# sensor_only.net
KiCad netlist of a schematic drawn in EAGLE
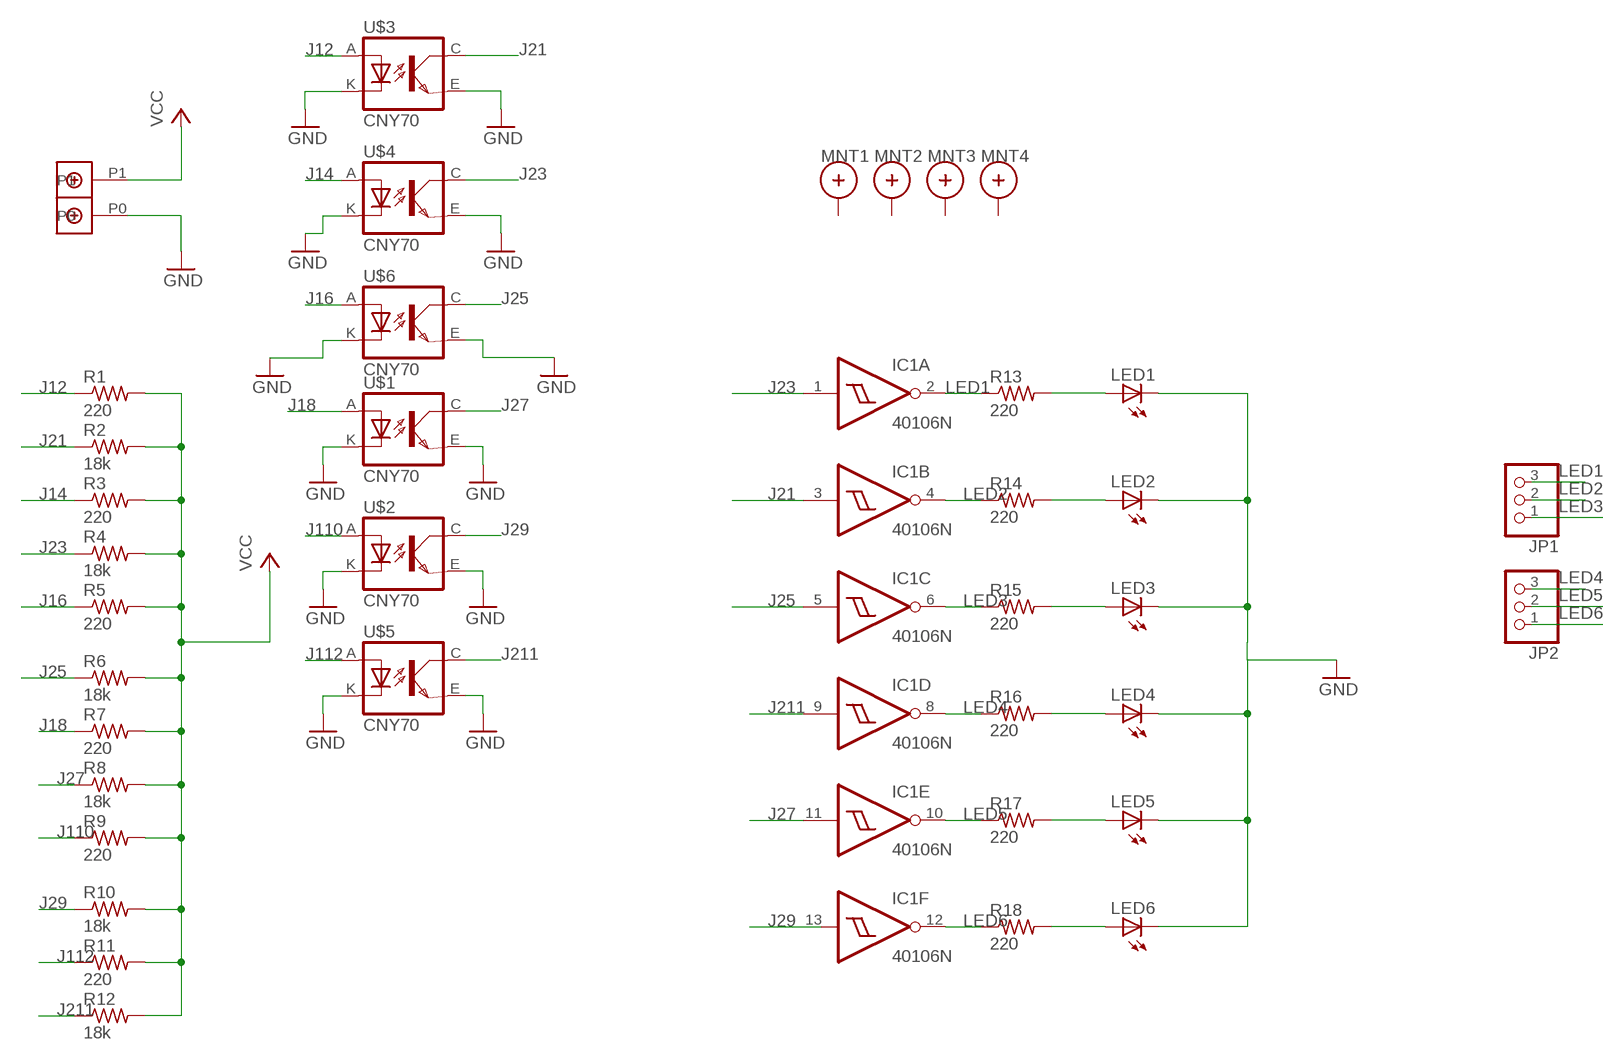
[diagram p0: schematic, sheet 1]

(export (version "E")
  (design (tool "Eeschema 10.0.6"))
  (components
    (comp (ref "IC1")
      (value "40106N")
      (footprint "eagle-import:DIL14")
      (libsource (lib "eagle-import") (part "40106N"))
    )
    (comp (ref "JP1")
      (value "PINHD-1X3")
      (footprint "eagle-import:1X03")
      (libsource (lib "eagle-import") (part "PINHD-1X3"))
    )
    (comp (ref "JP2")
      (value "PINHD-1X3")
      (footprint "eagle-import:1X03")
      (libsource (lib "eagle-import") (part "PINHD-1X3"))
    )
    (comp (ref "LED1")
      (value "LEDCHIPLED_1206")
      (footprint "eagle-import:CHIPLED_1206")
      (libsource (lib "eagle-import") (part "LEDCHIPLED_1206"))
    )
    (comp (ref "LED2")
      (value "LEDCHIPLED_1206")
      (footprint "eagle-import:CHIPLED_1206")
      (libsource (lib "eagle-import") (part "LEDCHIPLED_1206"))
    )
    (comp (ref "LED3")
      (value "LEDCHIPLED_1206")
      (footprint "eagle-import:CHIPLED_1206")
      (libsource (lib "eagle-import") (part "LEDCHIPLED_1206"))
    )
    (comp (ref "LED4")
      (value "LEDCHIPLED_1206")
      (footprint "eagle-import:CHIPLED_1206")
      (libsource (lib "eagle-import") (part "LEDCHIPLED_1206"))
    )
    (comp (ref "LED5")
      (value "LEDCHIPLED_1206")
      (footprint "eagle-import:CHIPLED_1206")
      (libsource (lib "eagle-import") (part "LEDCHIPLED_1206"))
    )
    (comp (ref "LED6")
      (value "LEDCHIPLED_1206")
      (footprint "eagle-import:CHIPLED_1206")
      (libsource (lib "eagle-import") (part "LEDCHIPLED_1206"))
    )
    (comp (ref "MNT1")
      (value "HOLE_MNT_0.135")
      (footprint "eagle-import:HOLE_MNT_#5-40")
      (libsource (lib "eagle-import") (part "HOLE_MNT_0.135"))
    )
    (comp (ref "MNT2")
      (value "HOLE_MNT_0.135")
      (footprint "eagle-import:HOLE_MNT_#5-40")
      (libsource (lib "eagle-import") (part "HOLE_MNT_0.135"))
    )
    (comp (ref "MNT3")
      (value "HOLE_MNT_0.135")
      (footprint "eagle-import:HOLE_MNT_#5-40")
      (libsource (lib "eagle-import") (part "HOLE_MNT_0.135"))
    )
    (comp (ref "MNT4")
      (value "HOLE_MNT_0.135")
      (footprint "eagle-import:HOLE_MNT_#5-40")
      (libsource (lib "eagle-import") (part "HOLE_MNT_0.135"))
    )
    (comp (ref "R1")
      (value "220")
      (footprint "eagle-import:M1206")
      (libsource (lib "eagle-import") (part "R-US_M1206"))
    )
    (comp (ref "R2")
      (value "18k")
      (footprint "eagle-import:M1206")
      (libsource (lib "eagle-import") (part "R-US_M1206"))
    )
    (comp (ref "R3")
      (value "220")
      (footprint "eagle-import:M1206")
      (libsource (lib "eagle-import") (part "R-US_M1206"))
    )
    (comp (ref "R4")
      (value "18k")
      (footprint "eagle-import:M1206")
      (libsource (lib "eagle-import") (part "R-US_M1206"))
    )
    (comp (ref "R5")
      (value "220")
      (footprint "eagle-import:M1206")
      (libsource (lib "eagle-import") (part "R-US_M1206"))
    )
    (comp (ref "R6")
      (value "18k")
      (footprint "eagle-import:M1206")
      (libsource (lib "eagle-import") (part "R-US_M1206"))
    )
    (comp (ref "R7")
      (value "220")
      (footprint "eagle-import:M1206")
      (libsource (lib "eagle-import") (part "R-US_M1206"))
    )
    (comp (ref "R8")
      (value "18k")
      (footprint "eagle-import:M1206")
      (libsource (lib "eagle-import") (part "R-US_M1206"))
    )
    (comp (ref "R9")
      (value "220")
      (footprint "eagle-import:M1206")
      (libsource (lib "eagle-import") (part "R-US_M1206"))
    )
    (comp (ref "R10")
      (value "18k")
      (footprint "eagle-import:M1206")
      (libsource (lib "eagle-import") (part "R-US_M1206"))
    )
    (comp (ref "R11")
      (value "220")
      (footprint "eagle-import:M1206")
      (libsource (lib "eagle-import") (part "R-US_M1206"))
    )
    (comp (ref "R12")
      (value "18k")
      (footprint "eagle-import:M1206")
      (libsource (lib "eagle-import") (part "R-US_M1206"))
    )
    (comp (ref "R13")
      (value "220")
      (footprint "eagle-import:M1206")
      (libsource (lib "eagle-import") (part "R-US_M1206"))
    )
    (comp (ref "R14")
      (value "220")
      (footprint "eagle-import:M1206")
      (libsource (lib "eagle-import") (part "R-US_M1206"))
    )
    (comp (ref "R15")
      (value "220")
      (footprint "eagle-import:M1206")
      (libsource (lib "eagle-import") (part "R-US_M1206"))
    )
    (comp (ref "R16")
      (value "220")
      (footprint "eagle-import:M1206")
      (libsource (lib "eagle-import") (part "R-US_M1206"))
    )
    (comp (ref "R17")
      (value "220")
      (footprint "eagle-import:M1206")
      (libsource (lib "eagle-import") (part "R-US_M1206"))
    )
    (comp (ref "R18")
      (value "220")
      (footprint "eagle-import:M1206")
      (libsource (lib "eagle-import") (part "R-US_M1206"))
    )
    (comp (ref "U$1")
      (value "CNY70")
      (footprint "eagle-import:4")
      (libsource (lib "eagle-import") (part "CNY70"))
    )
    (comp (ref "U$2")
      (value "CNY70")
      (footprint "eagle-import:4")
      (libsource (lib "eagle-import") (part "CNY70"))
    )
    (comp (ref "U$3")
      (value "CNY70")
      (footprint "eagle-import:4")
      (libsource (lib "eagle-import") (part "CNY70"))
    )
    (comp (ref "U$4")
      (value "CNY70")
      (footprint "eagle-import:4")
      (libsource (lib "eagle-import") (part "CNY70"))
    )
    (comp (ref "U$5")
      (value "CNY70")
      (footprint "eagle-import:4")
      (libsource (lib "eagle-import") (part "CNY70"))
    )
    (comp (ref "U$6")
      (value "CNY70")
      (footprint "eagle-import:4")
      (libsource (lib "eagle-import") (part "CNY70"))
    )
    (comp (ref "U$7")
      (value "DBCONN-1X2")
      (footprint "eagle-import:DBCONN-1X2")
      (libsource (lib "eagle-import") (part "DBCONN-1X2"))
    )
  )
  (nets
    (net (code "1") (name "/J12") (class "Default")
      (node (ref "R1") (pin "1") (pinfunction "1_1") (pintype "passive"))
      (node (ref "U$3") (pin "A") (pinfunction "A_A") (pintype "passive"))
    )
    (net (code "2") (name "/J14") (class "Default")
      (node (ref "R3") (pin "1") (pinfunction "1_1") (pintype "passive"))
      (node (ref "U$4") (pin "A") (pinfunction "A_A") (pintype "passive"))
    )
    (net (code "3") (name "/J16") (class "Default")
      (node (ref "R5") (pin "1") (pinfunction "1_1") (pintype "passive"))
      (node (ref "U$6") (pin "A") (pinfunction "A_A") (pintype "passive"))
    )
    (net (code "4") (name "/J18") (class "Default")
      (node (ref "R7") (pin "1") (pinfunction "1_1") (pintype "passive"))
      (node (ref "U$1") (pin "A") (pinfunction "A_A") (pintype "passive"))
    )
    (net (code "5") (name "/J21") (class "Default")
      (node (ref "IC1") (pin "3") (pinfunction "I_3") (pintype "input"))
      (node (ref "R2") (pin "1") (pinfunction "1_1") (pintype "passive"))
      (node (ref "U$3") (pin "C") (pinfunction "COL_C") (pintype "passive"))
    )
    (net (code "6") (name "/J23") (class "Default")
      (node (ref "IC1") (pin "1") (pinfunction "I_1") (pintype "input"))
      (node (ref "R4") (pin "1") (pinfunction "1_1") (pintype "passive"))
      (node (ref "U$4") (pin "C") (pinfunction "COL_C") (pintype "passive"))
    )
    (net (code "7") (name "/J25") (class "Default")
      (node (ref "IC1") (pin "5") (pinfunction "I_5") (pintype "input"))
      (node (ref "R6") (pin "1") (pinfunction "1_1") (pintype "passive"))
      (node (ref "U$6") (pin "C") (pinfunction "COL_C") (pintype "passive"))
    )
    (net (code "8") (name "/J27") (class "Default")
      (node (ref "IC1") (pin "11") (pinfunction "I_11") (pintype "input"))
      (node (ref "R8") (pin "1") (pinfunction "1_1") (pintype "passive"))
      (node (ref "U$1") (pin "C") (pinfunction "COL_C") (pintype "passive"))
    )
    (net (code "9") (name "/J29") (class "Default")
      (node (ref "R10") (pin "1") (pinfunction "1_1") (pintype "passive"))
      (node (ref "U$2") (pin "C") (pinfunction "COL_C") (pintype "passive"))
    )
    (net (code "10") (name "/J110") (class "Default")
      (node (ref "R9") (pin "1") (pinfunction "1_1") (pintype "passive"))
      (node (ref "U$2") (pin "A") (pinfunction "A_A") (pintype "passive"))
    )
    (net (code "11") (name "/J112") (class "Default")
      (node (ref "R11") (pin "1") (pinfunction "1_1") (pintype "passive"))
      (node (ref "U$5") (pin "A") (pinfunction "A_A") (pintype "passive"))
    )
    (net (code "12") (name "/J211") (class "Default")
      (node (ref "IC1") (pin "9") (pinfunction "I_9") (pintype "input"))
      (node (ref "R12") (pin "1") (pinfunction "1_1") (pintype "passive"))
      (node (ref "U$5") (pin "C") (pinfunction "COL_C") (pintype "passive"))
    )
    (net (code "13") (name "/LED1") (class "Default")
      (node (ref "IC1") (pin "2") (pinfunction "O_2") (pintype "output"))
      (node (ref "JP1") (pin "3") (pinfunction "3_3") (pintype "passive"))
      (node (ref "R13") (pin "1") (pinfunction "1_1") (pintype "passive"))
    )
    (net (code "14") (name "/LED2") (class "Default")
      (node (ref "IC1") (pin "4") (pinfunction "O_4") (pintype "output"))
      (node (ref "JP1") (pin "2") (pinfunction "2_2") (pintype "passive"))
      (node (ref "R14") (pin "1") (pinfunction "1_1") (pintype "passive"))
    )
    (net (code "15") (name "/LED3") (class "Default")
      (node (ref "IC1") (pin "6") (pinfunction "O_6") (pintype "output"))
      (node (ref "JP1") (pin "1") (pinfunction "1_1") (pintype "passive"))
      (node (ref "R15") (pin "1") (pinfunction "1_1") (pintype "passive"))
    )
    (net (code "16") (name "/LED4") (class "Default")
      (node (ref "IC1") (pin "8") (pinfunction "O_8") (pintype "output"))
      (node (ref "JP2") (pin "3") (pinfunction "3_3") (pintype "passive"))
      (node (ref "R16") (pin "1") (pinfunction "1_1") (pintype "passive"))
    )
    (net (code "17") (name "/LED5") (class "Default")
      (node (ref "IC1") (pin "10") (pinfunction "O_10") (pintype "output"))
      (node (ref "JP2") (pin "2") (pinfunction "2_2") (pintype "passive"))
      (node (ref "R17") (pin "1") (pinfunction "1_1") (pintype "passive"))
    )
    (net (code "18") (name "/LED6") (class "Default")
      (node (ref "IC1") (pin "12") (pinfunction "O_12") (pintype "output"))
      (node (ref "JP2") (pin "1") (pinfunction "1_1") (pintype "passive"))
      (node (ref "R18") (pin "1") (pinfunction "1_1") (pintype "passive"))
    )
    (net (code "19") (name "GND") (class "Default")
      (node (ref "LED1") (pin "C") (pinfunction "C_C") (pintype "passive"))
      (node (ref "LED2") (pin "C") (pinfunction "C_C") (pintype "passive"))
      (node (ref "LED3") (pin "C") (pinfunction "C_C") (pintype "passive"))
      (node (ref "LED4") (pin "C") (pinfunction "C_C") (pintype "passive"))
      (node (ref "LED5") (pin "C") (pinfunction "C_C") (pintype "passive"))
      (node (ref "LED6") (pin "C") (pinfunction "C_C") (pintype "passive"))
      (node (ref "U$1") (pin "E") (pinfunction "EMI_E") (pintype "passive"))
      (node (ref "U$1") (pin "K") (pinfunction "C_K") (pintype "passive"))
      (node (ref "U$2") (pin "E") (pinfunction "EMI_E") (pintype "passive"))
      (node (ref "U$2") (pin "K") (pinfunction "C_K") (pintype "passive"))
      (node (ref "U$3") (pin "E") (pinfunction "EMI_E") (pintype "passive"))
      (node (ref "U$3") (pin "K") (pinfunction "C_K") (pintype "passive"))
      (node (ref "U$4") (pin "E") (pinfunction "EMI_E") (pintype "passive"))
      (node (ref "U$4") (pin "K") (pinfunction "C_K") (pintype "passive"))
      (node (ref "U$5") (pin "E") (pinfunction "EMI_E") (pintype "passive"))
      (node (ref "U$5") (pin "K") (pinfunction "C_K") (pintype "passive"))
      (node (ref "U$6") (pin "E") (pinfunction "EMI_E") (pintype "passive"))
      (node (ref "U$6") (pin "K") (pinfunction "C_K") (pintype "passive"))
      (node (ref "U$7") (pin "P0") (pinfunction "P0_P0") (pintype "bidirectional"))
    )
    (net (code "20") (name "Net-(LED1-PadA)") (class "Default")
      (node (ref "LED1") (pin "A") (pinfunction "A_A") (pintype "passive"))
      (node (ref "R13") (pin "2") (pinfunction "2_2") (pintype "passive"))
    )
    (net (code "21") (name "Net-(LED2-PadA)") (class "Default")
      (node (ref "LED2") (pin "A") (pinfunction "A_A") (pintype "passive"))
      (node (ref "R14") (pin "2") (pinfunction "2_2") (pintype "passive"))
    )
    (net (code "22") (name "Net-(LED3-PadA)") (class "Default")
      (node (ref "LED3") (pin "A") (pinfunction "A_A") (pintype "passive"))
      (node (ref "R15") (pin "2") (pinfunction "2_2") (pintype "passive"))
    )
    (net (code "23") (name "Net-(LED4-PadA)") (class "Default")
      (node (ref "LED4") (pin "A") (pinfunction "A_A") (pintype "passive"))
      (node (ref "R16") (pin "2") (pinfunction "2_2") (pintype "passive"))
    )
    (net (code "24") (name "Net-(LED5-PadA)") (class "Default")
      (node (ref "LED5") (pin "A") (pinfunction "A_A") (pintype "passive"))
      (node (ref "R17") (pin "2") (pinfunction "2_2") (pintype "passive"))
    )
    (net (code "25") (name "Net-(LED6-PadA)") (class "Default")
      (node (ref "LED6") (pin "A") (pinfunction "A_A") (pintype "passive"))
      (node (ref "R18") (pin "2") (pinfunction "2_2") (pintype "passive"))
    )
    (net (code "26") (name "VCC") (class "Default")
      (node (ref "R1") (pin "2") (pinfunction "2_2") (pintype "passive"))
      (node (ref "R10") (pin "2") (pinfunction "2_2") (pintype "passive"))
      (node (ref "R11") (pin "2") (pinfunction "2_2") (pintype "passive"))
      (node (ref "R12") (pin "2") (pinfunction "2_2") (pintype "passive"))
      (node (ref "R2") (pin "2") (pinfunction "2_2") (pintype "passive"))
      (node (ref "R3") (pin "2") (pinfunction "2_2") (pintype "passive"))
      (node (ref "R4") (pin "2") (pinfunction "2_2") (pintype "passive"))
      (node (ref "R5") (pin "2") (pinfunction "2_2") (pintype "passive"))
      (node (ref "R6") (pin "2") (pinfunction "2_2") (pintype "passive"))
      (node (ref "R7") (pin "2") (pinfunction "2_2") (pintype "passive"))
      (node (ref "R8") (pin "2") (pinfunction "2_2") (pintype "passive"))
      (node (ref "R9") (pin "2") (pinfunction "2_2") (pintype "passive"))
      (node (ref "U$7") (pin "P1") (pinfunction "P1_P1") (pintype "bidirectional"))
    )
    (net (code "27") (name "unconnected-(IC1F-I-Pad13)") (class "Default")
      (node (ref "IC1") (pin "13") (pinfunction "I_13") (pintype "input"))
    )
    (net (code "28") (name "unconnected-(MNT1-1-PadP$1)") (class "Default")
      (node (ref "MNT1") (pin "P$1") (pinfunction "1_P$1") (pintype "bidirectional"))
    )
    (net (code "29") (name "unconnected-(MNT2-1-PadP$1)") (class "Default")
      (node (ref "MNT2") (pin "P$1") (pinfunction "1_P$1") (pintype "bidirectional"))
    )
    (net (code "30") (name "unconnected-(MNT3-1-PadP$1)") (class "Default")
      (node (ref "MNT3") (pin "P$1") (pinfunction "1_P$1") (pintype "bidirectional"))
    )
    (net (code "31") (name "unconnected-(MNT4-1-PadP$1)") (class "Default")
      (node (ref "MNT4") (pin "P$1") (pinfunction "1_P$1") (pintype "bidirectional"))
    )
  )
)
